# upconvertersch.net
KiCad netlist of a schematic drawn in EAGLE
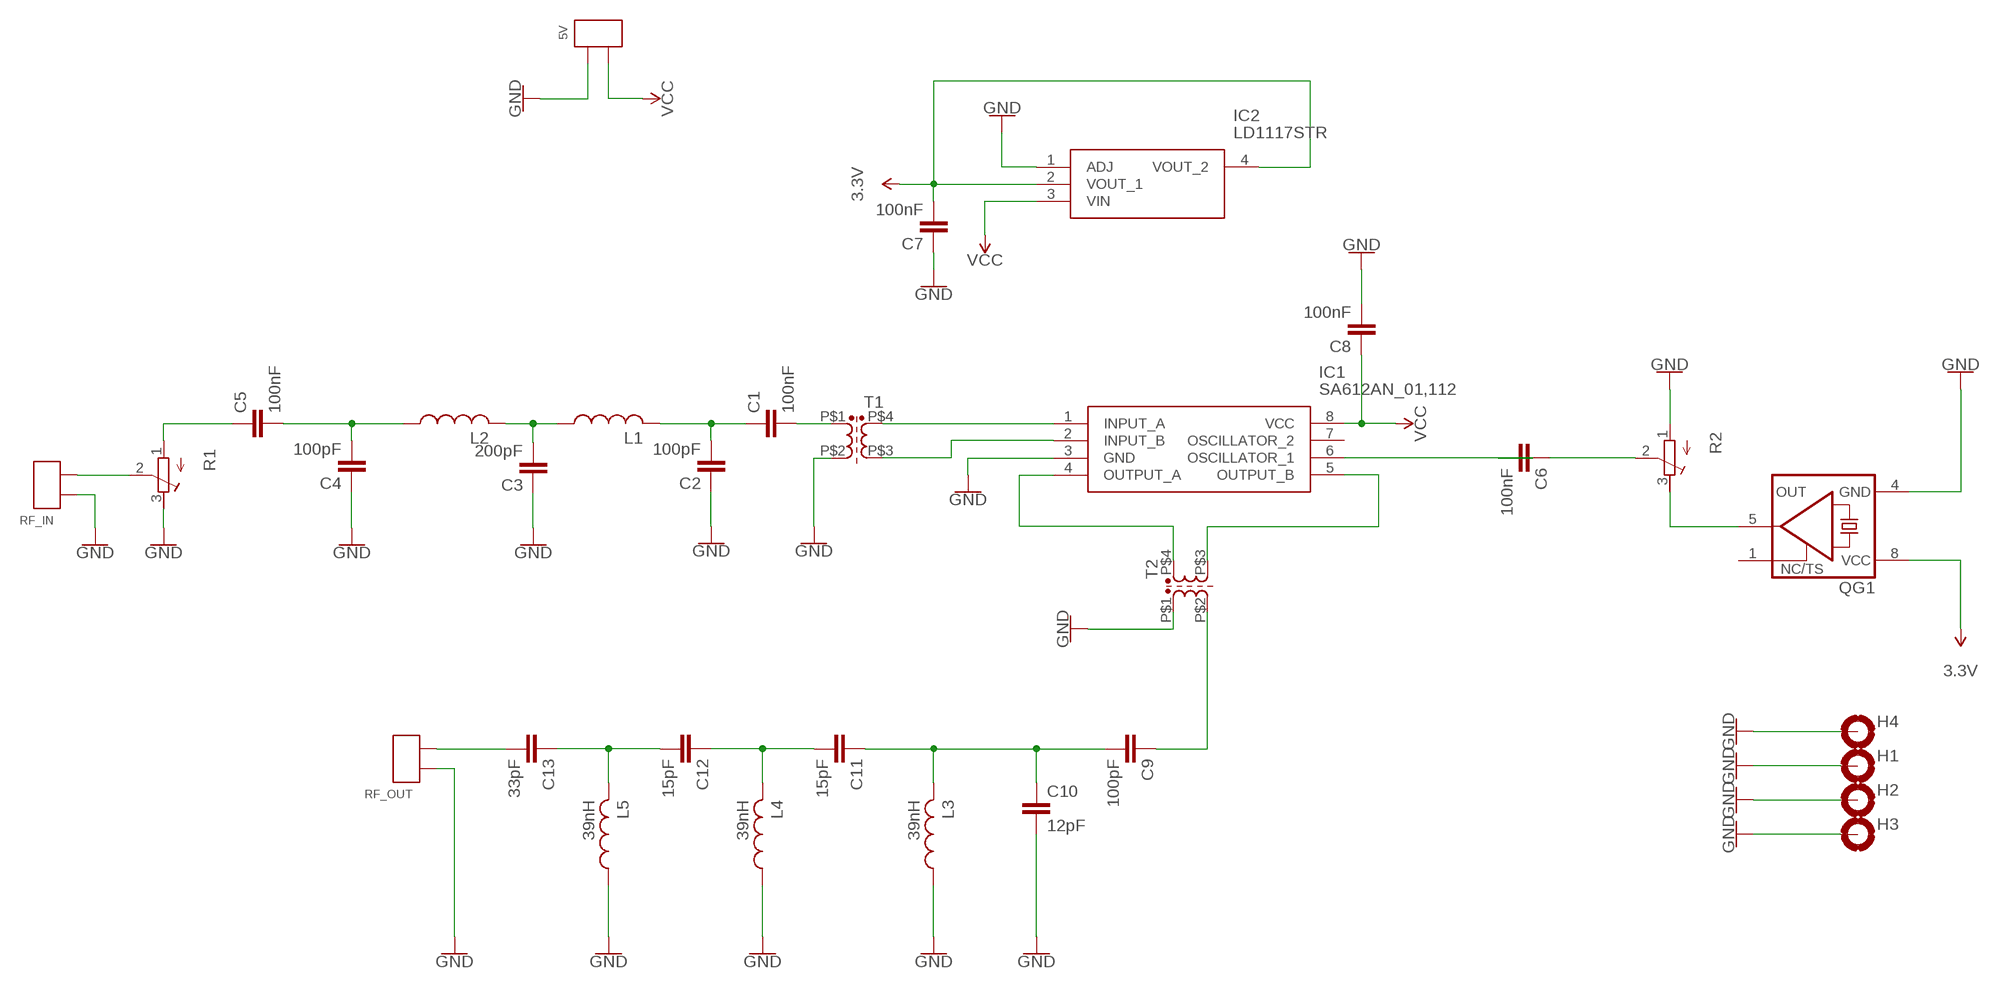
[diagram p0: schematic, sheet 1]

(export (version "E")
  (design (tool "Eeschema 10.0.6"))
  (components
    (comp (ref "5V")
      (value "2X_SMD_PTH_PIN")
      (footprint "eagle-import:2X_SMD_PTH")
      (libsource (lib "eagle-import") (part "2X_SMD_PTH_PIN"))
    )
    (comp (ref "C1")
      (value "100nF")
      (footprint "eagle-import:C0805K")
      (libsource (lib "eagle-import") (part "C_0805_PTH"))
    )
    (comp (ref "C2")
      (value "100pF")
      (footprint "eagle-import:C0805K")
      (libsource (lib "eagle-import") (part "C_0805_PTH"))
    )
    (comp (ref "C3")
      (value "200pF")
      (footprint "eagle-import:C0805K")
      (libsource (lib "eagle-import") (part "C_0805_PTH"))
    )
    (comp (ref "C4")
      (value "100pF")
      (footprint "eagle-import:C0805K")
      (libsource (lib "eagle-import") (part "C_0805_PTH"))
    )
    (comp (ref "C5")
      (value "100nF")
      (footprint "eagle-import:C0805K")
      (libsource (lib "eagle-import") (part "C_0805_PTH"))
    )
    (comp (ref "C6")
      (value "100nF")
      (footprint "eagle-import:C0805K")
      (libsource (lib "eagle-import") (part "C_0805_PTH"))
    )
    (comp (ref "C7")
      (value "100nF")
      (footprint "eagle-import:C0805K")
      (libsource (lib "eagle-import") (part "C_0805_PTH"))
    )
    (comp (ref "C8")
      (value "100nF")
      (footprint "eagle-import:C0805K")
      (libsource (lib "eagle-import") (part "C_0805_PTH"))
    )
    (comp (ref "C9")
      (value "100pF")
      (footprint "eagle-import:C0805K")
      (libsource (lib "eagle-import") (part "C_0805_PTH"))
    )
    (comp (ref "C10")
      (value "12pF")
      (footprint "eagle-import:C0805K")
      (libsource (lib "eagle-import") (part "C_0805_PTH"))
    )
    (comp (ref "C11")
      (value "15pF")
      (footprint "eagle-import:C0805K")
      (libsource (lib "eagle-import") (part "C_0805_PTH"))
    )
    (comp (ref "C12")
      (value "15pF")
      (footprint "eagle-import:C0805K")
      (libsource (lib "eagle-import") (part "C_0805_PTH"))
    )
    (comp (ref "C13")
      (value "33pF")
      (footprint "eagle-import:C0805K")
      (libsource (lib "eagle-import") (part "C_0805_PTH"))
    )
    (comp (ref "H1")
      (value "MOUNT-PAD-ROUND3.0")
      (footprint "eagle-import:3,0-PAD")
      (libsource (lib "eagle-import") (part "MOUNT-PAD-ROUND3.0"))
    )
    (comp (ref "H2")
      (value "MOUNT-PAD-ROUND3.0")
      (footprint "eagle-import:3,0-PAD")
      (libsource (lib "eagle-import") (part "MOUNT-PAD-ROUND3.0"))
    )
    (comp (ref "H3")
      (value "MOUNT-PAD-ROUND3.0")
      (footprint "eagle-import:3,0-PAD")
      (libsource (lib "eagle-import") (part "MOUNT-PAD-ROUND3.0"))
    )
    (comp (ref "H4")
      (value "MOUNT-PAD-ROUND3.0")
      (footprint "eagle-import:3,0-PAD")
      (libsource (lib "eagle-import") (part "MOUNT-PAD-ROUND3.0"))
    )
    (comp (ref "IC1")
      (value "SA612AN_01,112")
      (footprint "eagle-import:DIP762W53P254L950H420Q8N")
      (fields
        (field (name "MANUFACTURER_PART_NUMBER") "SA612AN/01,112")
        (field (name "MOUSER_PART_NUMBER") "771-SA612AN/01")
      )
      (libsource (lib "eagle-import") (part "SA612AN_01,112"))
    )
    (comp (ref "IC2")
      (value "LD1117STR")
      (footprint "eagle-import:SOT230P700X180-4N")
      (fields (field (name "MOUSER_PART_NUMBER") "511-LD1117S"))
      (libsource (lib "eagle-import") (part "LD1117STR"))
    )
    (comp (ref "L1")
      (value "L_0805_PTH")
      (footprint "eagle-import:M0805")
      (libsource (lib "eagle-import") (part "L_0805_PTH"))
    )
    (comp (ref "L2")
      (value "L_0805_PTH")
      (footprint "eagle-import:M0805")
      (libsource (lib "eagle-import") (part "L_0805_PTH"))
    )
    (comp (ref "L3")
      (value "39nH")
      (footprint "eagle-import:M0805")
      (libsource (lib "eagle-import") (part "L_0805_PTH"))
    )
    (comp (ref "L4")
      (value "39nH")
      (footprint "eagle-import:M0805")
      (libsource (lib "eagle-import") (part "L_0805_PTH"))
    )
    (comp (ref "L5")
      (value "39nH")
      (footprint "eagle-import:M0805")
      (libsource (lib "eagle-import") (part "L_0805_PTH"))
    )
    (comp (ref "QG1")
      (value "XO-8")
      (footprint "eagle-import:DIL08S")
      (libsource (lib "eagle-import") (part "XO-8"))
    )
    (comp (ref "R1")
      (value "R-TRIMM64W")
      (footprint "eagle-import:RTRIM64W")
      (libsource (lib "eagle-import") (part "R-TRIMM64W"))
    )
    (comp (ref "R2")
      (value "R-TRIMM64W")
      (footprint "eagle-import:RTRIM64W")
      (libsource (lib "eagle-import") (part "R-TRIMM64W"))
    )
    (comp (ref "RF_IN")
      (value "2X_SMD_PTH_PIN")
      (footprint "eagle-import:2X_SMD_PTH")
      (libsource (lib "eagle-import") (part "2X_SMD_PTH_PIN"))
    )
    (comp (ref "RF_OUT")
      (value "2X_SMD_PTH_PIN")
      (footprint "eagle-import:2X_SMD_PTH")
      (libsource (lib "eagle-import") (part "2X_SMD_PTH_PIN"))
    )
    (comp (ref "T1")
      (value "TRANSFORMER")
      (footprint "eagle-import:TRANSFORMER")
      (libsource (lib "eagle-import") (part "TRANSFORMER"))
    )
    (comp (ref "T2")
      (value "TRANSFORMER")
      (footprint "eagle-import:TRANSFORMER")
      (libsource (lib "eagle-import") (part "TRANSFORMER"))
    )
  )
  (nets
    (net (code "1") (name "3.3V") (class "Default")
      (node (ref "C7") (pin "2") (pinfunction "2_2") (pintype "passive"))
      (node (ref "C7") (pin "P$2") (pinfunction "2_P$2") (pintype "passive"))
      (node (ref "IC2") (pin "2") (pinfunction "VOUT_1_2") (pintype "bidirectional"))
      (node (ref "IC2") (pin "4") (pinfunction "VOUT_2_4") (pintype "bidirectional"))
      (node (ref "QG1") (pin "8") (pinfunction "VCC_8") (pintype "power_in"))
    )
    (net (code "2") (name "GND") (class "Default")
      (node (ref "5V") (pin "P$1") (pinfunction "PIN0_P$1") (pintype "bidirectional"))
      (node (ref "5V") (pin "T$1") (pinfunction "PIN0_T$1") (pintype "bidirectional"))
      (node (ref "C10") (pin "2") (pinfunction "2_2") (pintype "passive"))
      (node (ref "C10") (pin "P$2") (pinfunction "2_P$2") (pintype "passive"))
      (node (ref "C2") (pin "1") (pinfunction "1_1") (pintype "passive"))
      (node (ref "C2") (pin "P$1") (pinfunction "1_P$1") (pintype "passive"))
      (node (ref "C3") (pin "1") (pinfunction "1_1") (pintype "passive"))
      (node (ref "C3") (pin "P$1") (pinfunction "1_P$1") (pintype "passive"))
      (node (ref "C4") (pin "1") (pinfunction "1_1") (pintype "passive"))
      (node (ref "C4") (pin "P$1") (pinfunction "1_P$1") (pintype "passive"))
      (node (ref "C7") (pin "1") (pinfunction "1_1") (pintype "passive"))
      (node (ref "C7") (pin "P$1") (pinfunction "1_P$1") (pintype "passive"))
      (node (ref "C8") (pin "2") (pinfunction "2_2") (pintype "passive"))
      (node (ref "C8") (pin "P$2") (pinfunction "2_P$2") (pintype "passive"))
      (node (ref "H1") (pin "B3,0") (pinfunction "MOUNT_B3,0") (pintype "passive"))
      (node (ref "H2") (pin "B3,0") (pinfunction "MOUNT_B3,0") (pintype "passive"))
      (node (ref "H3") (pin "B3,0") (pinfunction "MOUNT_B3,0") (pintype "passive"))
      (node (ref "H4") (pin "B3,0") (pinfunction "MOUNT_B3,0") (pintype "passive"))
      (node (ref "IC1") (pin "3") (pinfunction "GND_3") (pintype "bidirectional"))
      (node (ref "IC2") (pin "1") (pinfunction "ADJ_1") (pintype "bidirectional"))
      (node (ref "L3") (pin "1") (pinfunction "1_1") (pintype "passive"))
      (node (ref "L3") (pin "P$1") (pinfunction "1_P$1") (pintype "passive"))
      (node (ref "L4") (pin "1") (pinfunction "1_1") (pintype "passive"))
      (node (ref "L4") (pin "P$1") (pinfunction "1_P$1") (pintype "passive"))
      (node (ref "L5") (pin "1") (pinfunction "1_1") (pintype "passive"))
      (node (ref "L5") (pin "P$1") (pinfunction "1_P$1") (pintype "passive"))
      (node (ref "QG1") (pin "4") (pinfunction "GND_4") (pintype "power_in"))
      (node (ref "R1") (pin "3") (pinfunction "E_3") (pintype "passive"))
      (node (ref "R2") (pin "1") (pinfunction "A_1") (pintype "passive"))
      (node (ref "RF_IN") (pin "P$1") (pinfunction "PIN0_P$1") (pintype "bidirectional"))
      (node (ref "RF_IN") (pin "T$1") (pinfunction "PIN0_T$1") (pintype "bidirectional"))
      (node (ref "RF_OUT") (pin "P$1") (pinfunction "PIN0_P$1") (pintype "bidirectional"))
      (node (ref "RF_OUT") (pin "T$1") (pinfunction "PIN0_T$1") (pintype "bidirectional"))
      (node (ref "T1") (pin "P$2") (pinfunction "4_P$2") (pintype "passive"))
      (node (ref "T2") (pin "P$1") (pinfunction "1_P$1") (pintype "passive"))
    )
    (net (code "3") (name "Net-(C1-1-PadP$1)") (class "Default")
      (node (ref "C1") (pin "1") (pinfunction "1_1") (pintype "passive"))
      (node (ref "C1") (pin "P$1") (pinfunction "1_P$1") (pintype "passive"))
      (node (ref "C2") (pin "2") (pinfunction "2_2") (pintype "passive"))
      (node (ref "C2") (pin "P$2") (pinfunction "2_P$2") (pintype "passive"))
      (node (ref "L1") (pin "2") (pinfunction "2_2") (pintype "passive"))
      (node (ref "L1") (pin "P$2") (pinfunction "2_P$2") (pintype "passive"))
    )
    (net (code "4") (name "Net-(C3-2-PadP$2)") (class "Default")
      (node (ref "C3") (pin "2") (pinfunction "2_2") (pintype "passive"))
      (node (ref "C3") (pin "P$2") (pinfunction "2_P$2") (pintype "passive"))
      (node (ref "L1") (pin "1") (pinfunction "1_1") (pintype "passive"))
      (node (ref "L1") (pin "P$1") (pinfunction "1_P$1") (pintype "passive"))
      (node (ref "L2") (pin "2") (pinfunction "2_2") (pintype "passive"))
      (node (ref "L2") (pin "P$2") (pinfunction "2_P$2") (pintype "passive"))
    )
    (net (code "5") (name "Net-(C4-2-PadP$2)") (class "Default")
      (node (ref "C4") (pin "2") (pinfunction "2_2") (pintype "passive"))
      (node (ref "C4") (pin "P$2") (pinfunction "2_P$2") (pintype "passive"))
      (node (ref "C5") (pin "2") (pinfunction "2_2") (pintype "passive"))
      (node (ref "C5") (pin "P$2") (pinfunction "2_P$2") (pintype "passive"))
      (node (ref "L2") (pin "1") (pinfunction "1_1") (pintype "passive"))
      (node (ref "L2") (pin "P$1") (pinfunction "1_P$1") (pintype "passive"))
    )
    (net (code "6") (name "Net-(C10-1-PadP$1)") (class "Default")
      (node (ref "C10") (pin "1") (pinfunction "1_1") (pintype "passive"))
      (node (ref "C10") (pin "P$1") (pinfunction "1_P$1") (pintype "passive"))
      (node (ref "C11") (pin "1") (pinfunction "1_1") (pintype "passive"))
      (node (ref "C11") (pin "P$1") (pinfunction "1_P$1") (pintype "passive"))
      (node (ref "C9") (pin "2") (pinfunction "2_2") (pintype "passive"))
      (node (ref "C9") (pin "P$2") (pinfunction "2_P$2") (pintype "passive"))
      (node (ref "L3") (pin "2") (pinfunction "2_2") (pintype "passive"))
      (node (ref "L3") (pin "P$2") (pinfunction "2_P$2") (pintype "passive"))
    )
    (net (code "7") (name "Net-(C11-2-PadP$2)") (class "Default")
      (node (ref "C11") (pin "2") (pinfunction "2_2") (pintype "passive"))
      (node (ref "C11") (pin "P$2") (pinfunction "2_P$2") (pintype "passive"))
      (node (ref "C12") (pin "1") (pinfunction "1_1") (pintype "passive"))
      (node (ref "C12") (pin "P$1") (pinfunction "1_P$1") (pintype "passive"))
      (node (ref "L4") (pin "2") (pinfunction "2_2") (pintype "passive"))
      (node (ref "L4") (pin "P$2") (pinfunction "2_P$2") (pintype "passive"))
    )
    (net (code "8") (name "Net-(C12-2-PadP$2)") (class "Default")
      (node (ref "C12") (pin "2") (pinfunction "2_2") (pintype "passive"))
      (node (ref "C12") (pin "P$2") (pinfunction "2_P$2") (pintype "passive"))
      (node (ref "C13") (pin "1") (pinfunction "1_1") (pintype "passive"))
      (node (ref "C13") (pin "P$1") (pinfunction "1_P$1") (pintype "passive"))
      (node (ref "L5") (pin "2") (pinfunction "2_2") (pintype "passive"))
      (node (ref "L5") (pin "P$2") (pinfunction "2_P$2") (pintype "passive"))
    )
    (net (code "9") (name "Net-(C13-2-PadP$2)") (class "Default")
      (node (ref "C13") (pin "2") (pinfunction "2_2") (pintype "passive"))
      (node (ref "C13") (pin "P$2") (pinfunction "2_P$2") (pintype "passive"))
      (node (ref "RF_OUT") (pin "P$2") (pinfunction "PIN1_P$2") (pintype "bidirectional"))
      (node (ref "RF_OUT") (pin "T$2") (pinfunction "PIN1_T$2") (pintype "bidirectional"))
    )
    (net (code "10") (name "Net-(IC1-INPUT_A)") (class "Default")
      (node (ref "IC1") (pin "1") (pinfunction "INPUT_A_1") (pintype "bidirectional"))
      (node (ref "T1") (pin "P$4") (pinfunction "8_P$4") (pintype "passive"))
    )
    (net (code "11") (name "Net-(IC1-INPUT_B)") (class "Default")
      (node (ref "IC1") (pin "2") (pinfunction "INPUT_B_2") (pintype "bidirectional"))
      (node (ref "T1") (pin "P$3") (pinfunction "5_P$3") (pintype "passive"))
    )
    (net (code "12") (name "Net-(IC1-OSCILLATOR_1)") (class "Default")
      (node (ref "C6") (pin "2") (pinfunction "2_2") (pintype "passive"))
      (node (ref "C6") (pin "P$2") (pinfunction "2_P$2") (pintype "passive"))
      (node (ref "IC1") (pin "6") (pinfunction "OSCILLATOR_1_6") (pintype "bidirectional"))
    )
    (net (code "13") (name "Net-(IC1-OUTPUT_A)") (class "Default")
      (node (ref "IC1") (pin "4") (pinfunction "OUTPUT_A_4") (pintype "bidirectional"))
      (node (ref "T2") (pin "P$4") (pinfunction "8_P$4") (pintype "passive"))
    )
    (net (code "14") (name "Net-(IC1-OUTPUT_B)") (class "Default")
      (node (ref "IC1") (pin "5") (pinfunction "OUTPUT_B_5") (pintype "bidirectional"))
      (node (ref "T2") (pin "P$3") (pinfunction "5_P$3") (pintype "passive"))
    )
    (net (code "15") (name "Net-(QG1-OUT)") (class "Default")
      (node (ref "QG1") (pin "5") (pinfunction "OUT_5") (pintype "output"))
      (node (ref "R2") (pin "3") (pinfunction "E_3") (pintype "passive"))
    )
    (net (code "16") (name "Net-(R1-A)") (class "Default")
      (node (ref "C5") (pin "1") (pinfunction "1_1") (pintype "passive"))
      (node (ref "C5") (pin "P$1") (pinfunction "1_P$1") (pintype "passive"))
      (node (ref "R1") (pin "1") (pinfunction "A_1") (pintype "passive"))
    )
    (net (code "17") (name "Net-(R1-S)") (class "Default")
      (node (ref "R1") (pin "2") (pinfunction "S_2") (pintype "passive"))
      (node (ref "RF_IN") (pin "P$2") (pinfunction "PIN1_P$2") (pintype "bidirectional"))
      (node (ref "RF_IN") (pin "T$2") (pinfunction "PIN1_T$2") (pintype "bidirectional"))
    )
    (net (code "18") (name "Net-(R2-S)") (class "Default")
      (node (ref "C6") (pin "1") (pinfunction "1_1") (pintype "passive"))
      (node (ref "C6") (pin "P$1") (pinfunction "1_P$1") (pintype "passive"))
      (node (ref "R2") (pin "2") (pinfunction "S_2") (pintype "passive"))
    )
    (net (code "19") (name "Net-(T1-1)") (class "Default")
      (node (ref "C1") (pin "2") (pinfunction "2_2") (pintype "passive"))
      (node (ref "C1") (pin "P$2") (pinfunction "2_P$2") (pintype "passive"))
      (node (ref "T1") (pin "P$1") (pinfunction "1_P$1") (pintype "passive"))
    )
    (net (code "20") (name "Net-(T2-4)") (class "Default")
      (node (ref "C9") (pin "1") (pinfunction "1_1") (pintype "passive"))
      (node (ref "C9") (pin "P$1") (pinfunction "1_P$1") (pintype "passive"))
      (node (ref "T2") (pin "P$2") (pinfunction "4_P$2") (pintype "passive"))
    )
    (net (code "21") (name "VCC") (class "Default")
      (node (ref "5V") (pin "P$2") (pinfunction "PIN1_P$2") (pintype "bidirectional"))
      (node (ref "5V") (pin "T$2") (pinfunction "PIN1_T$2") (pintype "bidirectional"))
      (node (ref "C8") (pin "1") (pinfunction "1_1") (pintype "passive"))
      (node (ref "C8") (pin "P$1") (pinfunction "1_P$1") (pintype "passive"))
      (node (ref "IC1") (pin "8") (pinfunction "VCC_8") (pintype "bidirectional"))
      (node (ref "IC2") (pin "3") (pinfunction "VIN_3") (pintype "bidirectional"))
    )
    (net (code "22") (name "unconnected-(IC1-OSCILLATOR_2-Pad7)") (class "Default")
      (node (ref "IC1") (pin "7") (pinfunction "OSCILLATOR_2_7") (pintype "bidirectional"))
    )
    (net (code "23") (name "unconnected-(QG1-TS-Pad1)") (class "Default")
      (node (ref "QG1") (pin "1") (pinfunction "TS_1") (pintype "passive"))
    )
  )
)
